# boardBase.net
KiCad netlist of a schematic drawn in EAGLE
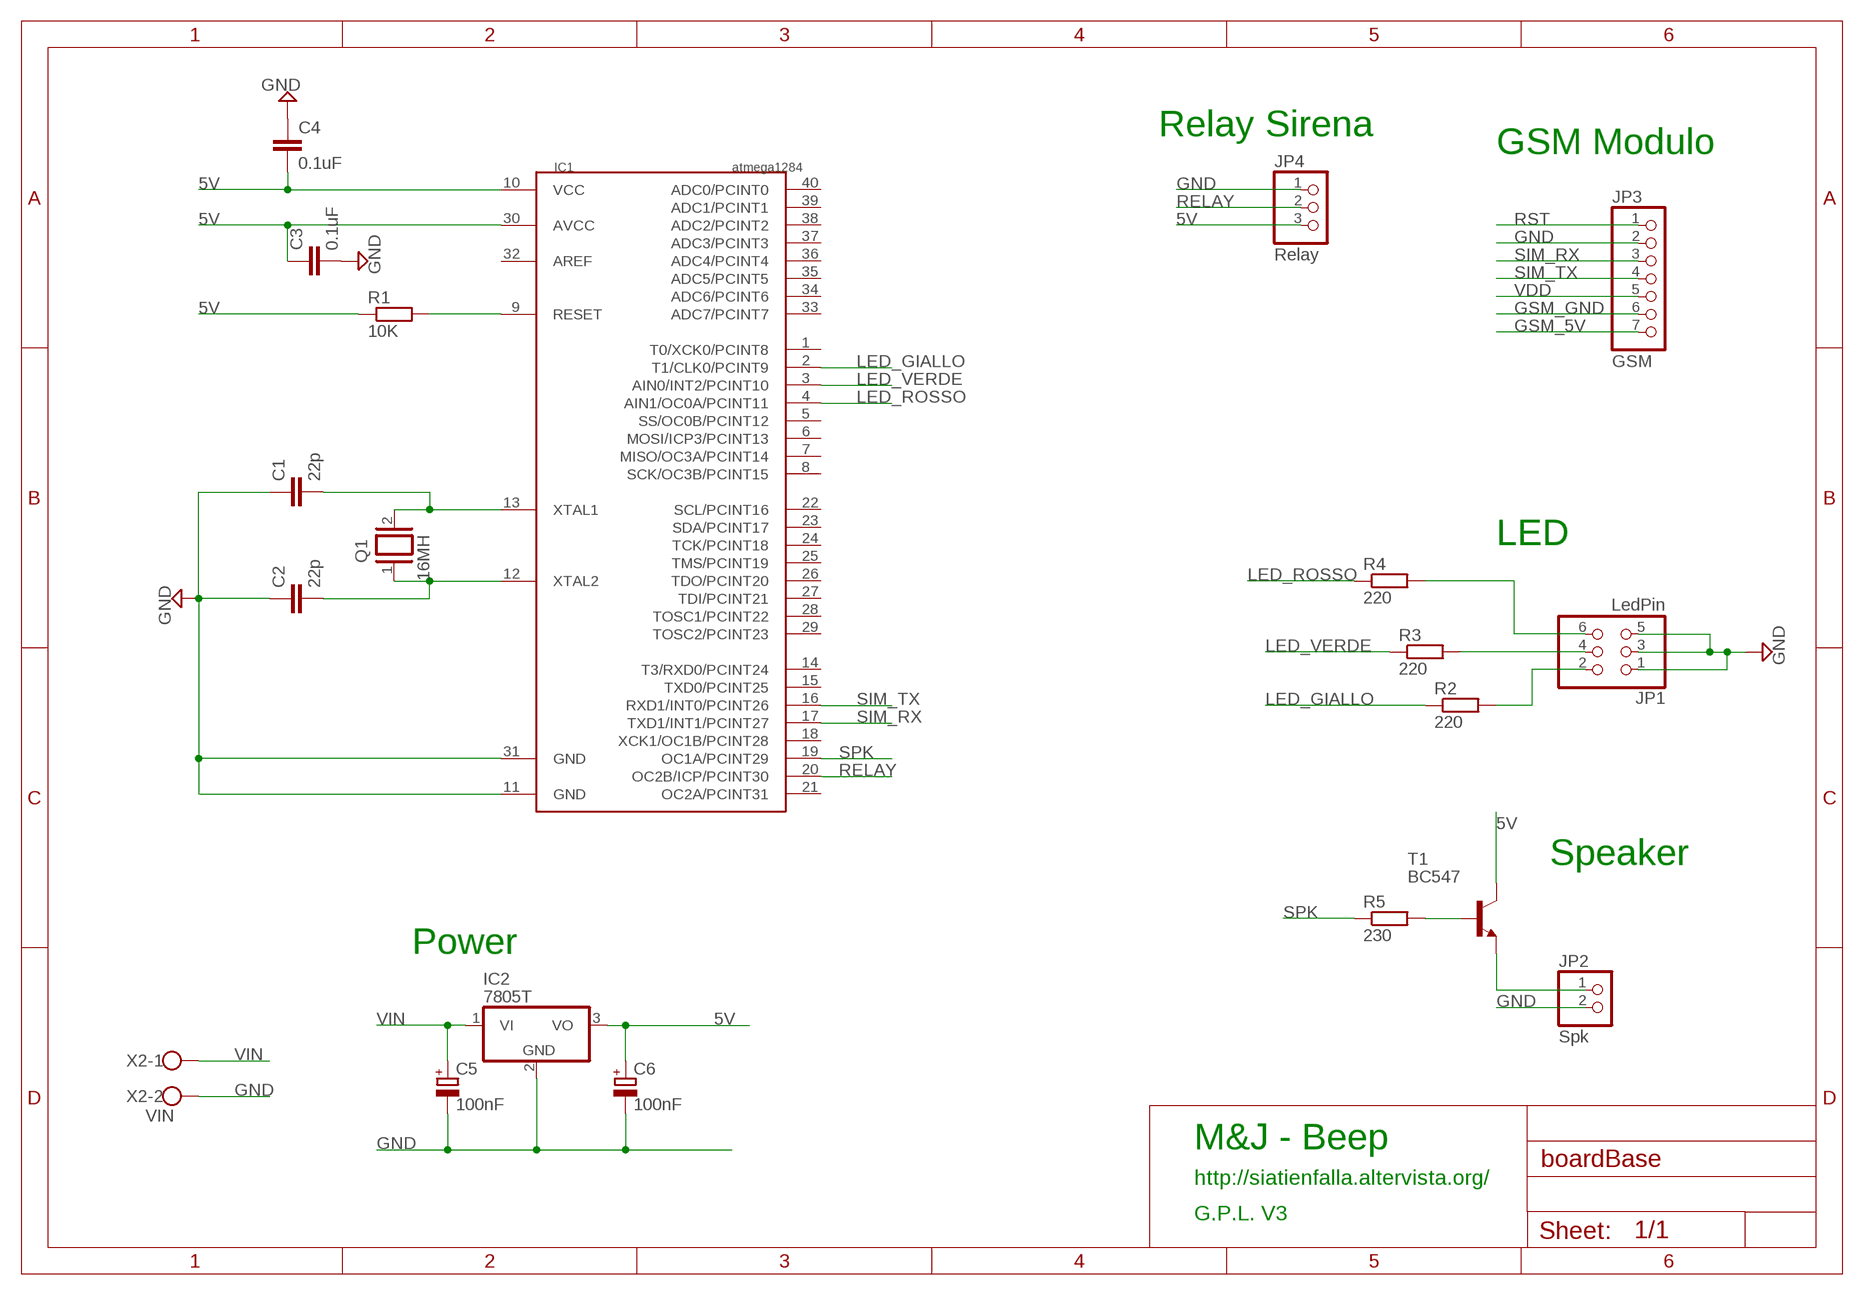
[diagram p0: schematic, sheet 1]

(export (version "E")
  (design (tool "Eeschema 10.0.6"))
  (components
    (comp (ref "C1")
      (value "22p")
      (footprint "eagle-import:C025-024X044")
      (libsource (lib "eagle-import") (part "C-EU025-024X044"))
    )
    (comp (ref "C2")
      (value "22p")
      (footprint "eagle-import:C025-024X044")
      (libsource (lib "eagle-import") (part "C-EU025-024X044"))
    )
    (comp (ref "C3")
      (value "0.1uF")
      (footprint "eagle-import:C025-025X050")
      (libsource (lib "eagle-import") (part "C-EU025-025X050"))
    )
    (comp (ref "C4")
      (value "0.1uF")
      (footprint "eagle-import:C025-025X050")
      (libsource (lib "eagle-import") (part "C-EU025-025X050"))
    )
    (comp (ref "C5")
      (value "100nF")
      (footprint "eagle-import:E3,5-10")
      (libsource (lib "eagle-import") (part "CPOL-EUE3.5-10"))
    )
    (comp (ref "C6")
      (value "100nF")
      (footprint "eagle-import:E3,5-10")
      (libsource (lib "eagle-import") (part "CPOL-EUE3.5-10"))
    )
    (comp (ref "IC1")
      (value "atmega1284")
      (footprint "eagle-import:DIL40")
      (libsource (lib "eagle-import") (part "MEGA1284P"))
    )
    (comp (ref "IC2")
      (value "7805T")
      (footprint "eagle-import:TO220H")
      (libsource (lib "eagle-import") (part "78T05"))
    )
    (comp (ref "JP1")
      (value "LedPin")
      (footprint "eagle-import:2X03")
      (libsource (lib "eagle-import") (part "PINHD-2X3"))
    )
    (comp (ref "JP2")
      (value "Spk")
      (footprint "eagle-import:1X02")
      (libsource (lib "eagle-import") (part "PINHD-1X2"))
    )
    (comp (ref "JP3")
      (value "GSM")
      (footprint "eagle-import:1X07")
      (libsource (lib "eagle-import") (part "PINHD-1X7"))
    )
    (comp (ref "JP4")
      (value "Relay")
      (footprint "eagle-import:1X03")
      (libsource (lib "eagle-import") (part "PINHD-1X3"))
    )
    (comp (ref "Q1")
      (value "16MH")
      (footprint "eagle-import:QS")
      (libsource (lib "eagle-import") (part "XTAL/S"))
    )
    (comp (ref "R1")
      (value "10K")
      (footprint "eagle-import:0207_10")
      (libsource (lib "eagle-import") (part "R-EU_0207/10"))
    )
    (comp (ref "R2")
      (value "220")
      (footprint "eagle-import:0207_10")
      (libsource (lib "eagle-import") (part "R-EU_0207/10"))
    )
    (comp (ref "R3")
      (value "220")
      (footprint "eagle-import:0207_10")
      (libsource (lib "eagle-import") (part "R-EU_0207/10"))
    )
    (comp (ref "R4")
      (value "220")
      (footprint "eagle-import:0207_10")
      (libsource (lib "eagle-import") (part "R-EU_0207/10"))
    )
    (comp (ref "R5")
      (value "230")
      (footprint "eagle-import:0207_10")
      (libsource (lib "eagle-import") (part "R-EU_0207/10"))
    )
    (comp (ref "T1")
      (value "BC547")
      (footprint "eagle-import:TO92")
      (libsource (lib "eagle-import") (part "BC547"))
    )
    (comp (ref "X2")
      (value "VIN")
      (footprint "eagle-import:W237-102")
      (fields (field (name "MPN") "237-102"))
      (libsource (lib "eagle-import") (part "W237-102"))
    )
  )
  (nets
    (net (code "1") (name "/5V") (class "Default")
      (node (ref "C3") (pin "1") (pinfunction "1_1") (pintype "passive"))
      (node (ref "C4") (pin "2") (pinfunction "2_2") (pintype "passive"))
      (node (ref "C6") (pin "+") (pinfunction "+_+") (pintype "passive"))
      (node (ref "IC1") (pin "10") (pinfunction "VCC_10") (pintype "bidirectional"))
      (node (ref "IC1") (pin "30") (pinfunction "AVCC_30") (pintype "bidirectional"))
      (node (ref "IC2") (pin "3") (pinfunction "VO_3") (pintype "passive"))
      (node (ref "JP4") (pin "3") (pinfunction "3_3") (pintype "passive"))
      (node (ref "R1") (pin "1") (pinfunction "1_1") (pintype "passive"))
      (node (ref "T1") (pin "3") (pinfunction "C_3") (pintype "passive"))
    )
    (net (code "2") (name "/GSM_5V") (class "Default")
      (node (ref "JP3") (pin "7") (pinfunction "7_7") (pintype "passive"))
    )
    (net (code "3") (name "/GSM_GND") (class "Default")
      (node (ref "JP3") (pin "6") (pinfunction "6_6") (pintype "passive"))
    )
    (net (code "4") (name "/LED_GIALLO") (class "Default")
      (node (ref "IC1") (pin "2") (pinfunction "T1/CLK0/PCINT9_2") (pintype "bidirectional"))
      (node (ref "R2") (pin "1") (pinfunction "1_1") (pintype "passive"))
    )
    (net (code "5") (name "/LED_ROSSO") (class "Default")
      (node (ref "IC1") (pin "4") (pinfunction "AIN1/OC0A/PCINT11_4") (pintype "bidirectional"))
      (node (ref "R4") (pin "1") (pinfunction "1_1") (pintype "passive"))
    )
    (net (code "6") (name "/LED_VERDE") (class "Default")
      (node (ref "IC1") (pin "3") (pinfunction "AIN0/INT2/PCINT10_3") (pintype "bidirectional"))
      (node (ref "R3") (pin "1") (pinfunction "1_1") (pintype "passive"))
    )
    (net (code "7") (name "/RELAY") (class "Default")
      (node (ref "IC1") (pin "20") (pinfunction "OC2B/ICP/PCINT30_20") (pintype "bidirectional"))
      (node (ref "JP4") (pin "2") (pinfunction "2_2") (pintype "passive"))
    )
    (net (code "8") (name "/RST") (class "Default")
      (node (ref "JP3") (pin "1") (pinfunction "1_1") (pintype "passive"))
    )
    (net (code "9") (name "/SIM_RX") (class "Default")
      (node (ref "IC1") (pin "17") (pinfunction "TXD1/INT1/PCINT27_17") (pintype "bidirectional"))
      (node (ref "JP3") (pin "3") (pinfunction "3_3") (pintype "passive"))
    )
    (net (code "10") (name "/SIM_TX") (class "Default")
      (node (ref "IC1") (pin "16") (pinfunction "RXD1/INT0/PCINT26_16") (pintype "bidirectional"))
      (node (ref "JP3") (pin "4") (pinfunction "4_4") (pintype "passive"))
    )
    (net (code "11") (name "/SPK") (class "Default")
      (node (ref "IC1") (pin "19") (pinfunction "OC1A/PCINT29_19") (pintype "bidirectional"))
      (node (ref "R5") (pin "1") (pinfunction "1_1") (pintype "passive"))
    )
    (net (code "12") (name "/VDD") (class "Default")
      (node (ref "JP3") (pin "5") (pinfunction "5_5") (pintype "passive"))
    )
    (net (code "13") (name "/VIN") (class "Default")
      (node (ref "C5") (pin "+") (pinfunction "+_+") (pintype "passive"))
      (node (ref "IC2") (pin "1") (pinfunction "VI_1") (pintype "input"))
      (node (ref "X2") (pin "1") (pinfunction "KL_1") (pintype "passive"))
    )
    (net (code "14") (name "GND") (class "Default")
      (node (ref "C1") (pin "1") (pinfunction "1_1") (pintype "passive"))
      (node (ref "C2") (pin "1") (pinfunction "1_1") (pintype "passive"))
      (node (ref "C3") (pin "2") (pinfunction "2_2") (pintype "passive"))
      (node (ref "C4") (pin "1") (pinfunction "1_1") (pintype "passive"))
      (node (ref "C5") (pin "-") (pinfunction "-_-") (pintype "passive"))
      (node (ref "C6") (pin "-") (pinfunction "-_-") (pintype "passive"))
      (node (ref "IC1") (pin "11") (pinfunction "GND_11") (pintype "bidirectional"))
      (node (ref "IC1") (pin "31") (pinfunction "GND_31") (pintype "bidirectional"))
      (node (ref "IC2") (pin "2") (pinfunction "GND_2") (pintype "passive"))
      (node (ref "JP1") (pin "1") (pinfunction "1_1") (pintype "passive"))
      (node (ref "JP1") (pin "3") (pinfunction "3_3") (pintype "passive"))
      (node (ref "JP1") (pin "5") (pinfunction "5_5") (pintype "passive"))
      (node (ref "JP2") (pin "2") (pinfunction "2_2") (pintype "passive"))
      (node (ref "JP3") (pin "2") (pinfunction "2_2") (pintype "passive"))
      (node (ref "JP4") (pin "1") (pinfunction "1_1") (pintype "passive"))
      (node (ref "X2") (pin "2") (pinfunction "KL_2") (pintype "passive"))
    )
    (net (code "15") (name "Net-(IC1-RESET)") (class "Default")
      (node (ref "IC1") (pin "9") (pinfunction "RESET_9") (pintype "bidirectional"))
      (node (ref "R1") (pin "2") (pinfunction "2_2") (pintype "passive"))
    )
    (net (code "16") (name "Net-(IC1-XTAL1)") (class "Default")
      (node (ref "C1") (pin "2") (pinfunction "2_2") (pintype "passive"))
      (node (ref "IC1") (pin "13") (pinfunction "XTAL1_13") (pintype "bidirectional"))
      (node (ref "Q1") (pin "2") (pinfunction "2_2") (pintype "passive"))
    )
    (net (code "17") (name "Net-(IC1-XTAL2)") (class "Default")
      (node (ref "C2") (pin "2") (pinfunction "2_2") (pintype "passive"))
      (node (ref "IC1") (pin "12") (pinfunction "XTAL2_12") (pintype "bidirectional"))
      (node (ref "Q1") (pin "1") (pinfunction "1_1") (pintype "passive"))
    )
    (net (code "18") (name "Net-(JP1-Pad2)") (class "Default")
      (node (ref "JP1") (pin "2") (pinfunction "2_2") (pintype "passive"))
      (node (ref "R2") (pin "2") (pinfunction "2_2") (pintype "passive"))
    )
    (net (code "19") (name "Net-(JP1-Pad4)") (class "Default")
      (node (ref "JP1") (pin "4") (pinfunction "4_4") (pintype "passive"))
      (node (ref "R3") (pin "2") (pinfunction "2_2") (pintype "passive"))
    )
    (net (code "20") (name "Net-(JP1-Pad6)") (class "Default")
      (node (ref "JP1") (pin "6") (pinfunction "6_6") (pintype "passive"))
      (node (ref "R4") (pin "2") (pinfunction "2_2") (pintype "passive"))
    )
    (net (code "21") (name "Net-(T1-B)") (class "Default")
      (node (ref "R5") (pin "2") (pinfunction "2_2") (pintype "passive"))
      (node (ref "T1") (pin "2") (pinfunction "B_2") (pintype "passive"))
    )
    (net (code "22") (name "Net-(T1-E)") (class "Default")
      (node (ref "JP2") (pin "1") (pinfunction "1_1") (pintype "passive"))
      (node (ref "T1") (pin "1") (pinfunction "E_1") (pintype "passive"))
    )
    (net (code "23") (name "unconnected-(IC1-ADC0{slash}PCINT0-Pad40)") (class "Default")
      (node (ref "IC1") (pin "40") (pinfunction "ADC0/PCINT0_40") (pintype "bidirectional"))
    )
    (net (code "24") (name "unconnected-(IC1-ADC1{slash}PCINT1-Pad39)") (class "Default")
      (node (ref "IC1") (pin "39") (pinfunction "ADC1/PCINT1_39") (pintype "bidirectional"))
    )
    (net (code "25") (name "unconnected-(IC1-ADC2{slash}PCINT2-Pad38)") (class "Default")
      (node (ref "IC1") (pin "38") (pinfunction "ADC2/PCINT2_38") (pintype "bidirectional"))
    )
    (net (code "26") (name "unconnected-(IC1-ADC3{slash}PCINT3-Pad37)") (class "Default")
      (node (ref "IC1") (pin "37") (pinfunction "ADC3/PCINT3_37") (pintype "bidirectional"))
    )
    (net (code "27") (name "unconnected-(IC1-ADC4{slash}PCINT4-Pad36)") (class "Default")
      (node (ref "IC1") (pin "36") (pinfunction "ADC4/PCINT4_36") (pintype "bidirectional"))
    )
    (net (code "28") (name "unconnected-(IC1-ADC5{slash}PCINT5-Pad35)") (class "Default")
      (node (ref "IC1") (pin "35") (pinfunction "ADC5/PCINT5_35") (pintype "bidirectional"))
    )
    (net (code "29") (name "unconnected-(IC1-ADC6{slash}PCINT6-Pad34)") (class "Default")
      (node (ref "IC1") (pin "34") (pinfunction "ADC6/PCINT6_34") (pintype "bidirectional"))
    )
    (net (code "30") (name "unconnected-(IC1-ADC7{slash}PCINT7-Pad33)") (class "Default")
      (node (ref "IC1") (pin "33") (pinfunction "ADC7/PCINT7_33") (pintype "bidirectional"))
    )
    (net (code "31") (name "unconnected-(IC1-AREF-Pad32)") (class "Default")
      (node (ref "IC1") (pin "32") (pinfunction "AREF_32") (pintype "bidirectional"))
    )
    (net (code "32") (name "unconnected-(IC1-MISO{slash}OC3A{slash}PCINT14-Pad7)") (class "Default")
      (node (ref "IC1") (pin "7") (pinfunction "MISO/OC3A/PCINT14_7") (pintype "bidirectional"))
    )
    (net (code "33") (name "unconnected-(IC1-MOSI{slash}ICP3{slash}PCINT13-Pad6)") (class "Default")
      (node (ref "IC1") (pin "6") (pinfunction "MOSI/ICP3/PCINT13_6") (pintype "bidirectional"))
    )
    (net (code "34") (name "unconnected-(IC1-OC2A{slash}PCINT31-Pad21)") (class "Default")
      (node (ref "IC1") (pin "21") (pinfunction "OC2A/PCINT31_21") (pintype "bidirectional"))
    )
    (net (code "35") (name "unconnected-(IC1-SCK{slash}OC3B{slash}PCINT15-Pad8)") (class "Default")
      (node (ref "IC1") (pin "8") (pinfunction "SCK/OC3B/PCINT15_8") (pintype "bidirectional"))
    )
    (net (code "36") (name "unconnected-(IC1-SCL{slash}PCINT16-Pad22)") (class "Default")
      (node (ref "IC1") (pin "22") (pinfunction "SCL/PCINT16_22") (pintype "bidirectional"))
    )
    (net (code "37") (name "unconnected-(IC1-SDA{slash}PCINT17-Pad23)") (class "Default")
      (node (ref "IC1") (pin "23") (pinfunction "SDA/PCINT17_23") (pintype "bidirectional"))
    )
    (net (code "38") (name "unconnected-(IC1-SS{slash}OC0B{slash}PCINT12-Pad5)") (class "Default")
      (node (ref "IC1") (pin "5") (pinfunction "SS/OC0B/PCINT12_5") (pintype "bidirectional"))
    )
    (net (code "39") (name "unconnected-(IC1-T0{slash}XCK0{slash}PCINT8-Pad1)") (class "Default")
      (node (ref "IC1") (pin "1") (pinfunction "T0/XCK0/PCINT8_1") (pintype "bidirectional"))
    )
    (net (code "40") (name "unconnected-(IC1-T3{slash}RXD0{slash}PCINT24-Pad14)") (class "Default")
      (node (ref "IC1") (pin "14") (pinfunction "T3/RXD0/PCINT24_14") (pintype "bidirectional"))
    )
    (net (code "41") (name "unconnected-(IC1-TCK{slash}PCINT18-Pad24)") (class "Default")
      (node (ref "IC1") (pin "24") (pinfunction "TCK/PCINT18_24") (pintype "bidirectional"))
    )
    (net (code "42") (name "unconnected-(IC1-TDI{slash}PCINT21-Pad27)") (class "Default")
      (node (ref "IC1") (pin "27") (pinfunction "TDI/PCINT21_27") (pintype "bidirectional"))
    )
    (net (code "43") (name "unconnected-(IC1-TDO{slash}PCINT20-Pad26)") (class "Default")
      (node (ref "IC1") (pin "26") (pinfunction "TDO/PCINT20_26") (pintype "bidirectional"))
    )
    (net (code "44") (name "unconnected-(IC1-TMS{slash}PCINT19-Pad25)") (class "Default")
      (node (ref "IC1") (pin "25") (pinfunction "TMS/PCINT19_25") (pintype "bidirectional"))
    )
    (net (code "45") (name "unconnected-(IC1-TOSC1{slash}PCINT22-Pad28)") (class "Default")
      (node (ref "IC1") (pin "28") (pinfunction "TOSC1/PCINT22_28") (pintype "bidirectional"))
    )
    (net (code "46") (name "unconnected-(IC1-TOSC2{slash}PCINT23-Pad29)") (class "Default")
      (node (ref "IC1") (pin "29") (pinfunction "TOSC2/PCINT23_29") (pintype "bidirectional"))
    )
    (net (code "47") (name "unconnected-(IC1-TXD0{slash}PCINT25-Pad15)") (class "Default")
      (node (ref "IC1") (pin "15") (pinfunction "TXD0/PCINT25_15") (pintype "bidirectional"))
    )
    (net (code "48") (name "unconnected-(IC1-XCK1{slash}OC1B{slash}PCINT28-Pad18)") (class "Default")
      (node (ref "IC1") (pin "18") (pinfunction "XCK1/OC1B/PCINT28_18") (pintype "bidirectional"))
    )
  )
)
